# HIP4082driver.net
KiCad netlist of a schematic drawn in Altium Designer
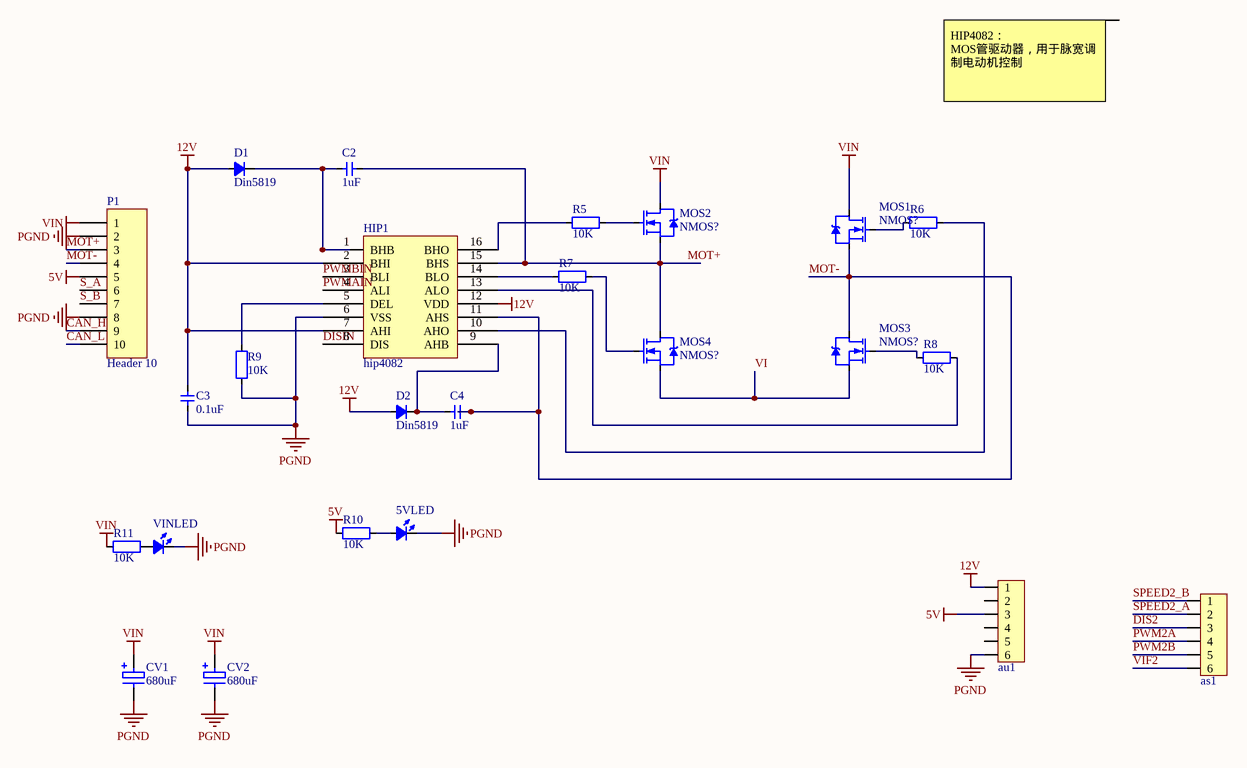
[diagram p0: HIP4082driver.SchDoc]

(export (version "E")
  (design (tool "Eeschema 10.0.6"))
  (components
    (comp (ref "5VLED")
      (value "LED_0805")
      (footprint "LED_0805_BLUE")
      (description "LED")
      (libsource (lib "SCH_Active") (part "LED_0603"))
    )
    (comp (ref "as1")
      (value "HDR1x6_2.54")
      (footprint "HDR1X6_2.54_180")
      (description "Header")
      (libsource (lib "Integrated_Library") (part "HDR1x6_2.54"))
    )
    (comp (ref "au1")
      (value "HDR1x6_2.54")
      (footprint "HDR1X6_2.54_180")
      (description "Header")
      (libsource (lib "Integrated_Library") (part "HDR1x6_2.54"))
    )
    (comp (ref "C2")
      (value "1uF")
      (footprint "CAP_0603")
      (description "Capacitor")
      (fields (field (name "Comment") "Cap_0603"))
      (libsource (lib "Integrated_Library") (part "Cap_0603"))
    )
    (comp (ref "C3")
      (value "0.1uF")
      (footprint "CAP_0603")
      (description "Capacitor")
      (fields (field (name "Comment") "Cap_0603"))
      (libsource (lib "Integrated_Library") (part "Cap_0603"))
    )
    (comp (ref "C4")
      (value "1uF")
      (footprint "CAP_0603")
      (description "Capacitor")
      (fields (field (name "Comment") "Cap_0603"))
      (libsource (lib "Integrated_Library") (part "Cap_0603"))
    )
    (comp (ref "CV1")
      (value "680uF")
      (footprint "CAP_ELE_680UF0.7X5MM")
      (description "电解电容")
      (fields (field (name "PUBLISHER") "Altium Limited"))
      (libsource (lib "Libraries_2014_0618") (part "CAP-ELE"))
    )
    (comp (ref "CV2")
      (value "680uF")
      (footprint "CAP_ELE_680UF0.7X5MM")
      (description "电解电容")
      (fields (field (name "PUBLISHER") "Altium Limited"))
      (libsource (lib "Libraries_2014_0618") (part "CAP-ELE"))
    )
    (comp (ref "D1")
      (value "Din5819")
      (footprint "SOD-323")
      (description "Diode")
      (libsource (lib "Integrated_Library") (part "Diode"))
    )
    (comp (ref "D2")
      (value "Din5819")
      (footprint "SOD-323")
      (description "Diode")
      (libsource (lib "Integrated_Library") (part "Diode"))
    )
    (comp (ref "HIP1") (value "hip4082") (footprint "SOP_E150_16") (libsource (lib "元件库") (part "hip4082")))
    (comp (ref "MOS1")
      (value "NMOS?")
      (footprint "PCB_IntegratedCircuit:TO-252AA")
      (description "MOSFET")
      (fields (field (name "Comment") "MOSFET_N"))
      (libsource (lib "SCH_Active") (part "MOSFET_N"))
    )
    (comp (ref "MOS2")
      (value "NMOS?")
      (footprint "PCB_IntegratedCircuit:TO-252AA")
      (description "MOSFET")
      (fields (field (name "Comment") "MOSFET_N"))
      (libsource (lib "SCH_Active") (part "MOSFET_N"))
    )
    (comp (ref "MOS3")
      (value "NMOS?")
      (footprint "PCB_IntegratedCircuit:TO-252AA")
      (description "MOSFET")
      (fields (field (name "Comment") "MOSFET_N"))
      (libsource (lib "SCH_Active") (part "MOSFET_N"))
    )
    (comp (ref "MOS4")
      (value "NMOS?")
      (footprint "PCB_IntegratedCircuit:TO-252AA")
      (description "MOSFET")
      (fields (field (name "Comment") "MOSFET_N"))
      (libsource (lib "SCH_Active") (part "MOSFET_N"))
    )
    (comp (ref "P1")
      (value "Header 10")
      (footprint "Green_10P")
      (description "Header, 10-Pin")
      (fields (field (name "PUBLISHER") "Altium Limited"))
      (libsource (lib "Libraries_2014_0618") (part "Header 10"))
    )
    (comp (ref "R5")
      (value "10K")
      (footprint "RES_0603")
      (description "Resistor")
      (fields (field (name "Comment") "Res_0603"))
      (libsource (lib "Integrated_Library") (part "Res_0603"))
    )
    (comp (ref "R6")
      (value "10K")
      (footprint "RES_0603")
      (description "Resistor")
      (fields (field (name "Comment") "Res_0603"))
      (libsource (lib "Integrated_Library") (part "Res_0603"))
    )
    (comp (ref "R7")
      (value "10K")
      (footprint "RES_0603")
      (description "Resistor")
      (fields (field (name "Comment") "Res_0603"))
      (libsource (lib "Integrated_Library") (part "Res_0603"))
    )
    (comp (ref "R8")
      (value "10K")
      (footprint "RES_0603")
      (description "Resistor")
      (fields (field (name "Comment") "Res_0603"))
      (libsource (lib "Integrated_Library") (part "Res_0603"))
    )
    (comp (ref "R9")
      (value "10K")
      (footprint "RES_0603")
      (description "Resistor")
      (fields (field (name "Comment") "Res_0603"))
      (libsource (lib "") (part "Res_0603_1"))
    )
    (comp (ref "R10")
      (value "10K")
      (footprint "RES_0603")
      (description "Resistor")
      (fields (field (name "Comment") "Res_0603"))
      (libsource (lib "Integrated_Library") (part "Res_0603"))
    )
    (comp (ref "R11")
      (value "10K")
      (footprint "RES_0603")
      (description "Resistor")
      (fields (field (name "Comment") "Res_0603"))
      (libsource (lib "Integrated_Library") (part "Res_0603"))
    )
    (comp (ref "VINLED")
      (value "LED_0805")
      (footprint "LED_0805_RED")
      (description "LED")
      (libsource (lib "SCH_Active") (part "LED_0603"))
    )
  )
  (nets
    (net (code "1") (name "/CAN_H") (class "Default")
      (node (ref "P1") (pin "9") (pinfunction "9_9") (pintype "passive"))
    )
    (net (code "2") (name "/CAN_L") (class "Default")
      (node (ref "P1") (pin "10") (pinfunction "10_10") (pintype "passive"))
    )
    (net (code "3") (name "/DIS2") (class "Default")
      (node (ref "as1") (pin "3") (pinfunction "3_3") (pintype "passive"))
    )
    (net (code "4") (name "/DISIN") (class "Default")
      (node (ref "HIP1") (pin "8") (pinfunction "DIS_8") (pintype "passive"))
    )
    (net (code "5") (name "/MOT+") (class "Default")
      (node (ref "C2") (pin "2") (pinfunction "2_2") (pintype "passive"))
      (node (ref "HIP1") (pin "15") (pinfunction "BHS_15") (pintype "passive"))
      (node (ref "MOS2") (pin "3") (pinfunction "S_3") (pintype "passive"))
      (node (ref "MOS4") (pin "4") (pinfunction "D_4") (pintype "passive"))
      (node (ref "P1") (pin "3") (pinfunction "3_3") (pintype "passive"))
    )
    (net (code "6") (name "/MOT-") (class "Default")
      (node (ref "C4") (pin "2") (pinfunction "2_2") (pintype "passive"))
      (node (ref "HIP1") (pin "11") (pinfunction "AHS_11") (pintype "passive"))
      (node (ref "MOS1") (pin "3") (pinfunction "S_3") (pintype "passive"))
      (node (ref "MOS3") (pin "4") (pinfunction "D_4") (pintype "passive"))
      (node (ref "P1") (pin "4") (pinfunction "4_4") (pintype "passive"))
    )
    (net (code "7") (name "/PWM2A") (class "Default")
      (node (ref "as1") (pin "4") (pinfunction "4_4") (pintype "passive"))
    )
    (net (code "8") (name "/PWM2B") (class "Default")
      (node (ref "as1") (pin "5") (pinfunction "5_5") (pintype "passive"))
    )
    (net (code "9") (name "/PWMAIN") (class "Default")
      (node (ref "HIP1") (pin "4") (pinfunction "ALI_4") (pintype "passive"))
    )
    (net (code "10") (name "/PWMBIN") (class "Default")
      (node (ref "HIP1") (pin "3") (pinfunction "BLI_3") (pintype "passive"))
    )
    (net (code "11") (name "/SPEED2_A") (class "Default")
      (node (ref "as1") (pin "2") (pinfunction "2_2") (pintype "passive"))
    )
    (net (code "12") (name "/SPEED2_B") (class "Default")
      (node (ref "as1") (pin "1") (pinfunction "1_1") (pintype "passive"))
    )
    (net (code "13") (name "/S_A") (class "Default")
      (node (ref "P1") (pin "6") (pinfunction "6_6") (pintype "passive"))
    )
    (net (code "14") (name "/S_B") (class "Default")
      (node (ref "P1") (pin "7") (pinfunction "7_7") (pintype "passive"))
    )
    (net (code "15") (name "/VI") (class "Default")
      (node (ref "MOS3") (pin "3") (pinfunction "S_3") (pintype "passive"))
      (node (ref "MOS4") (pin "3") (pinfunction "S_3") (pintype "passive"))
    )
    (net (code "16") (name "/VIF2") (class "Default")
      (node (ref "as1") (pin "6") (pinfunction "6_6") (pintype "passive"))
    )
    (net (code "17") (name "5V") (class "Default")
      (node (ref "P1") (pin "5") (pinfunction "5_5") (pintype "passive"))
      (node (ref "R10") (pin "1") (pinfunction "1_1") (pintype "passive"))
      (node (ref "au1") (pin "3") (pinfunction "3_3") (pintype "passive"))
    )
    (net (code "18") (name "12V") (class "Default")
      (node (ref "C3") (pin "2") (pinfunction "2_2") (pintype "passive"))
      (node (ref "D1") (pin "1") (pinfunction "A_1") (pintype "passive"))
      (node (ref "D2") (pin "1") (pinfunction "A_1") (pintype "passive"))
      (node (ref "HIP1") (pin "12") (pinfunction "VDD_12") (pintype "passive"))
      (node (ref "HIP1") (pin "2") (pinfunction "BHI_2") (pintype "passive"))
      (node (ref "HIP1") (pin "7") (pinfunction "AHI_7") (pintype "passive"))
      (node (ref "au1") (pin "1") (pinfunction "1_1") (pintype "passive"))
    )
    (net (code "19") (name "Net-(5VLED-A)") (class "Default")
      (node (ref "5VLED") (pin "1") (pinfunction "A_1") (pintype "passive"))
      (node (ref "R10") (pin "2") (pinfunction "2_2") (pintype "passive"))
    )
    (net (code "20") (name "Net-(D1-K)") (class "Default")
      (node (ref "C2") (pin "1") (pinfunction "1_1") (pintype "passive"))
      (node (ref "D1") (pin "2") (pinfunction "K_2") (pintype "passive"))
      (node (ref "HIP1") (pin "1") (pinfunction "BHB_1") (pintype "passive"))
    )
    (net (code "21") (name "Net-(D2-K)") (class "Default")
      (node (ref "C4") (pin "1") (pinfunction "1_1") (pintype "passive"))
      (node (ref "D2") (pin "2") (pinfunction "K_2") (pintype "passive"))
      (node (ref "HIP1") (pin "9") (pinfunction "AHB_9") (pintype "passive"))
    )
    (net (code "22") (name "Net-(HIP1-AHO)") (class "Default")
      (node (ref "HIP1") (pin "10") (pinfunction "AHO_10") (pintype "passive"))
      (node (ref "R6") (pin "2") (pinfunction "2_2") (pintype "passive"))
    )
    (net (code "23") (name "Net-(HIP1-ALO)") (class "Default")
      (node (ref "HIP1") (pin "13") (pinfunction "ALO_13") (pintype "passive"))
      (node (ref "R8") (pin "2") (pinfunction "2_2") (pintype "passive"))
    )
    (net (code "24") (name "Net-(HIP1-BHO)") (class "Default")
      (node (ref "HIP1") (pin "16") (pinfunction "BHO_16") (pintype "passive"))
      (node (ref "R5") (pin "1") (pinfunction "1_1") (pintype "passive"))
    )
    (net (code "25") (name "Net-(HIP1-BLO)") (class "Default")
      (node (ref "HIP1") (pin "14") (pinfunction "BLO_14") (pintype "passive"))
      (node (ref "R7") (pin "1") (pinfunction "1_1") (pintype "passive"))
    )
    (net (code "26") (name "Net-(HIP1-DEL)") (class "Default")
      (node (ref "HIP1") (pin "5") (pinfunction "DEL_5") (pintype "passive"))
      (node (ref "R9") (pin "2") (pinfunction "2_2") (pintype "passive"))
    )
    (net (code "27") (name "Net-(MOS1-G)") (class "Default")
      (node (ref "MOS1") (pin "1") (pinfunction "G_1") (pintype "passive"))
      (node (ref "R6") (pin "1") (pinfunction "1_1") (pintype "passive"))
    )
    (net (code "28") (name "Net-(MOS2-G)") (class "Default")
      (node (ref "MOS2") (pin "1") (pinfunction "G_1") (pintype "passive"))
      (node (ref "R5") (pin "2") (pinfunction "2_2") (pintype "passive"))
    )
    (net (code "29") (name "Net-(MOS3-G)") (class "Default")
      (node (ref "MOS3") (pin "1") (pinfunction "G_1") (pintype "passive"))
      (node (ref "R8") (pin "1") (pinfunction "1_1") (pintype "passive"))
    )
    (net (code "30") (name "Net-(MOS4-G)") (class "Default")
      (node (ref "MOS4") (pin "1") (pinfunction "G_1") (pintype "passive"))
      (node (ref "R7") (pin "2") (pinfunction "2_2") (pintype "passive"))
    )
    (net (code "31") (name "Net-(VINLED-A)") (class "Default")
      (node (ref "R11") (pin "2") (pinfunction "2_2") (pintype "passive"))
      (node (ref "VINLED") (pin "1") (pinfunction "A_1") (pintype "passive"))
    )
    (net (code "32") (name "PGND") (class "Default")
      (node (ref "5VLED") (pin "2") (pinfunction "K_2") (pintype "passive"))
      (node (ref "C3") (pin "1") (pinfunction "1_1") (pintype "passive"))
      (node (ref "CV1") (pin "2") (pinfunction "2_2") (pintype "passive"))
      (node (ref "CV2") (pin "2") (pinfunction "2_2") (pintype "passive"))
      (node (ref "HIP1") (pin "6") (pinfunction "VSS_6") (pintype "passive"))
      (node (ref "P1") (pin "2") (pinfunction "2_2") (pintype "passive"))
      (node (ref "P1") (pin "8") (pinfunction "8_8") (pintype "passive"))
      (node (ref "R9") (pin "1") (pinfunction "1_1") (pintype "passive"))
      (node (ref "VINLED") (pin "2") (pinfunction "K_2") (pintype "passive"))
      (node (ref "au1") (pin "6") (pinfunction "6_6") (pintype "passive"))
    )
    (net (code "33") (name "VIN") (class "Default")
      (node (ref "CV1") (pin "1") (pinfunction "1_1") (pintype "passive"))
      (node (ref "CV2") (pin "1") (pinfunction "1_1") (pintype "passive"))
      (node (ref "MOS1") (pin "4") (pinfunction "D_4") (pintype "passive"))
      (node (ref "MOS2") (pin "4") (pinfunction "D_4") (pintype "passive"))
      (node (ref "P1") (pin "1") (pinfunction "1_1") (pintype "passive"))
      (node (ref "R11") (pin "1") (pinfunction "1_1") (pintype "passive"))
    )
    (net (code "34") (name "unconnected-(au1-Pad2)") (class "Default")
      (node (ref "au1") (pin "2") (pinfunction "2_2") (pintype "passive"))
    )
    (net (code "35") (name "unconnected-(au1-Pad4)") (class "Default")
      (node (ref "au1") (pin "4") (pinfunction "4_4") (pintype "passive"))
    )
    (net (code "36") (name "unconnected-(au1-Pad5)") (class "Default")
      (node (ref "au1") (pin "5") (pinfunction "5_5") (pintype "passive"))
    )
  )
)
